# AP_AT42QT2120.net
KiCad netlist of a schematic drawn in EAGLE
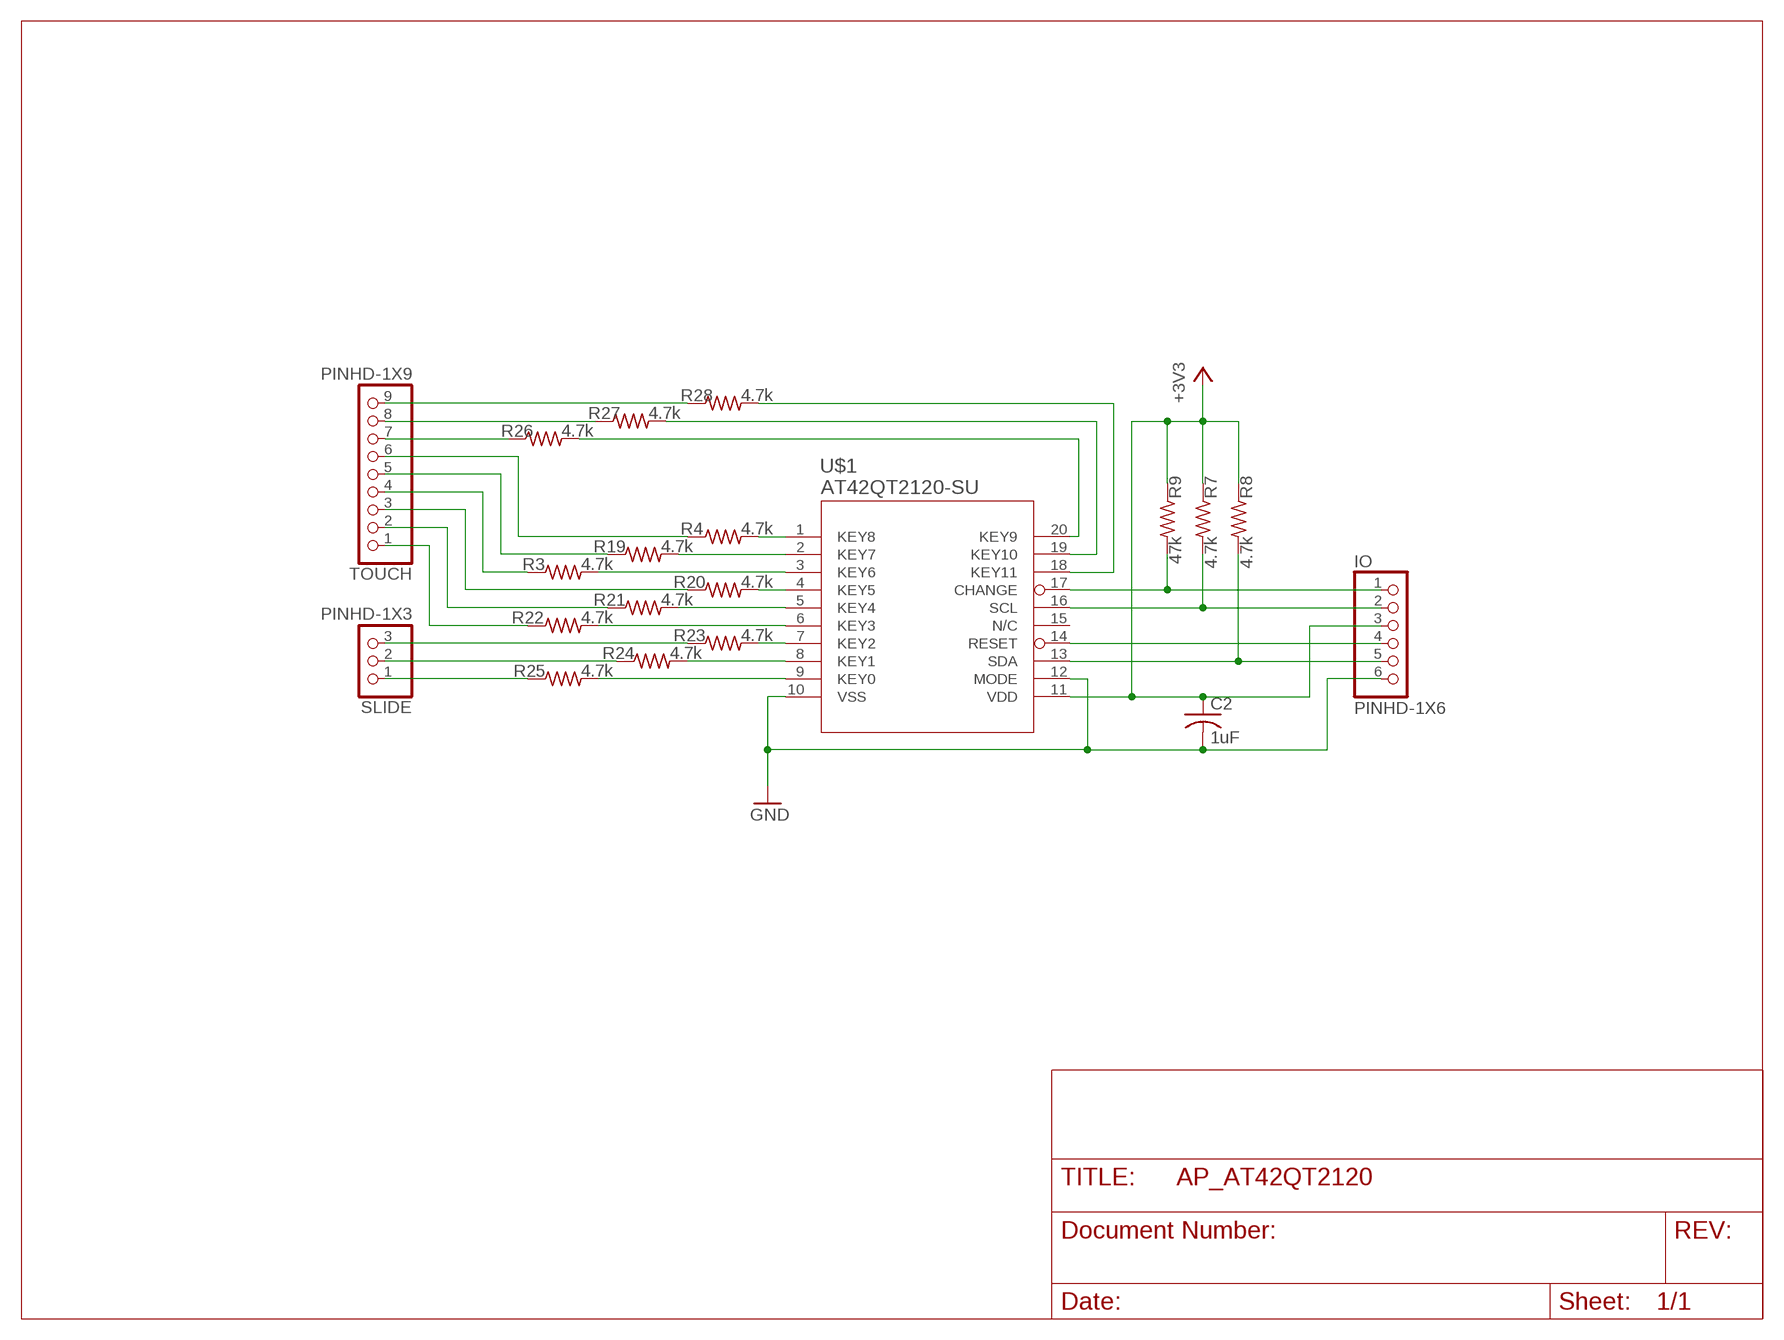
[diagram p0: schematic, sheet 1]

(export (version "E")
  (design (tool "Eeschema 10.0.6"))
  (components
    (comp (ref "C2")
      (value "1uF")
      (footprint "eagle-import:C1206")
      (libsource (lib "eagle-import") (part "C-USC1206"))
    )
    (comp (ref "IO")
      (value "PINHD-1X6")
      (footprint "eagle-import:1X06")
      (libsource (lib "eagle-import") (part "PINHD-1X6"))
    )
    (comp (ref "R3")
      (value "4.7k")
      (footprint "eagle-import:R1206")
      (libsource (lib "eagle-import") (part "R-US_R1206"))
    )
    (comp (ref "R4")
      (value "4.7k")
      (footprint "eagle-import:R1206")
      (libsource (lib "eagle-import") (part "R-US_R1206"))
    )
    (comp (ref "R7")
      (value "4.7k")
      (footprint "eagle-import:R1206")
      (libsource (lib "eagle-import") (part "R-US_R1206"))
    )
    (comp (ref "R8")
      (value "4.7k")
      (footprint "eagle-import:R1206")
      (libsource (lib "eagle-import") (part "R-US_R1206"))
    )
    (comp (ref "R9")
      (value "47k")
      (footprint "eagle-import:R1206")
      (libsource (lib "eagle-import") (part "R-US_R1206"))
    )
    (comp (ref "R19")
      (value "4.7k")
      (footprint "eagle-import:R1206")
      (libsource (lib "eagle-import") (part "R-US_R1206"))
    )
    (comp (ref "R20")
      (value "4.7k")
      (footprint "eagle-import:R1206")
      (libsource (lib "eagle-import") (part "R-US_R1206"))
    )
    (comp (ref "R21")
      (value "4.7k")
      (footprint "eagle-import:R1206")
      (libsource (lib "eagle-import") (part "R-US_R1206"))
    )
    (comp (ref "R22")
      (value "4.7k")
      (footprint "eagle-import:R1206")
      (libsource (lib "eagle-import") (part "R-US_R1206"))
    )
    (comp (ref "R23")
      (value "4.7k")
      (footprint "eagle-import:R1206")
      (libsource (lib "eagle-import") (part "R-US_R1206"))
    )
    (comp (ref "R24")
      (value "4.7k")
      (footprint "eagle-import:R1206")
      (libsource (lib "eagle-import") (part "R-US_R1206"))
    )
    (comp (ref "R25")
      (value "4.7k")
      (footprint "eagle-import:R1206")
      (libsource (lib "eagle-import") (part "R-US_R1206"))
    )
    (comp (ref "R26")
      (value "4.7k")
      (footprint "eagle-import:R1206")
      (libsource (lib "eagle-import") (part "R-US_R1206"))
    )
    (comp (ref "R27")
      (value "4.7k")
      (footprint "eagle-import:R1206")
      (libsource (lib "eagle-import") (part "R-US_R1206"))
    )
    (comp (ref "R28")
      (value "4.7k")
      (footprint "eagle-import:R1206")
      (libsource (lib "eagle-import") (part "R-US_R1206"))
    )
    (comp (ref "SLIDE")
      (value "PINHD-1X3")
      (footprint "eagle-import:1X03")
      (libsource (lib "eagle-import") (part "PINHD-1X3"))
    )
    (comp (ref "TOUCH")
      (value "PINHD-1X9")
      (footprint "eagle-import:1X09")
      (libsource (lib "eagle-import") (part "PINHD-1X9"))
    )
    (comp (ref "U$1")
      (value "AT42QT2120-SU")
      (footprint "eagle-import:SOIC20")
      (libsource (lib "eagle-import") (part "AT42QT2120-SU"))
    )
  )
  (nets
    (net (code "1") (name "+3V3") (class "Default")
      (node (ref "C2") (pin "1") (pinfunction "1_1") (pintype "passive"))
      (node (ref "IO") (pin "3") (pinfunction "3_3") (pintype "passive"))
      (node (ref "R7") (pin "1") (pinfunction "1_1") (pintype "passive"))
      (node (ref "R8") (pin "1") (pinfunction "1_1") (pintype "passive"))
      (node (ref "R9") (pin "1") (pinfunction "1_1") (pintype "passive"))
      (node (ref "U$1") (pin "11") (pinfunction "VDD_11") (pintype "power_in"))
    )
    (net (code "2") (name "GND") (class "Default")
      (node (ref "C2") (pin "2") (pinfunction "2_2") (pintype "passive"))
      (node (ref "IO") (pin "6") (pinfunction "6_6") (pintype "passive"))
      (node (ref "U$1") (pin "10") (pinfunction "VSS_10") (pintype "passive"))
      (node (ref "U$1") (pin "12") (pinfunction "MODE_12") (pintype "passive"))
    )
    (net (code "3") (name "Net-(R3-Pad1)") (class "Default")
      (node (ref "R3") (pin "1") (pinfunction "1_1") (pintype "passive"))
      (node (ref "TOUCH") (pin "4") (pinfunction "4_4") (pintype "passive"))
    )
    (net (code "4") (name "Net-(R4-Pad1)") (class "Default")
      (node (ref "R4") (pin "1") (pinfunction "1_1") (pintype "passive"))
      (node (ref "TOUCH") (pin "6") (pinfunction "6_6") (pintype "passive"))
    )
    (net (code "5") (name "Net-(R19-Pad1)") (class "Default")
      (node (ref "R19") (pin "1") (pinfunction "1_1") (pintype "passive"))
      (node (ref "TOUCH") (pin "5") (pinfunction "5_5") (pintype "passive"))
    )
    (net (code "6") (name "Net-(R20-Pad1)") (class "Default")
      (node (ref "R20") (pin "1") (pinfunction "1_1") (pintype "passive"))
      (node (ref "TOUCH") (pin "3") (pinfunction "3_3") (pintype "passive"))
    )
    (net (code "7") (name "Net-(R21-Pad1)") (class "Default")
      (node (ref "R21") (pin "1") (pinfunction "1_1") (pintype "passive"))
      (node (ref "TOUCH") (pin "2") (pinfunction "2_2") (pintype "passive"))
    )
    (net (code "8") (name "Net-(R22-Pad1)") (class "Default")
      (node (ref "R22") (pin "1") (pinfunction "1_1") (pintype "passive"))
      (node (ref "TOUCH") (pin "1") (pinfunction "1_1") (pintype "passive"))
    )
    (net (code "9") (name "Net-(R23-Pad1)") (class "Default")
      (node (ref "R23") (pin "1") (pinfunction "1_1") (pintype "passive"))
      (node (ref "SLIDE") (pin "3") (pinfunction "3_3") (pintype "passive"))
    )
    (net (code "10") (name "Net-(R24-Pad1)") (class "Default")
      (node (ref "R24") (pin "1") (pinfunction "1_1") (pintype "passive"))
      (node (ref "SLIDE") (pin "2") (pinfunction "2_2") (pintype "passive"))
    )
    (net (code "11") (name "Net-(R25-Pad1)") (class "Default")
      (node (ref "R25") (pin "1") (pinfunction "1_1") (pintype "passive"))
      (node (ref "SLIDE") (pin "1") (pinfunction "1_1") (pintype "passive"))
    )
    (net (code "12") (name "Net-(R26-Pad1)") (class "Default")
      (node (ref "R26") (pin "1") (pinfunction "1_1") (pintype "passive"))
      (node (ref "TOUCH") (pin "7") (pinfunction "7_7") (pintype "passive"))
    )
    (net (code "13") (name "Net-(R27-Pad1)") (class "Default")
      (node (ref "R27") (pin "1") (pinfunction "1_1") (pintype "passive"))
      (node (ref "TOUCH") (pin "8") (pinfunction "8_8") (pintype "passive"))
    )
    (net (code "14") (name "Net-(R28-Pad1)") (class "Default")
      (node (ref "R28") (pin "1") (pinfunction "1_1") (pintype "passive"))
      (node (ref "TOUCH") (pin "9") (pinfunction "9_9") (pintype "passive"))
    )
    (net (code "15") (name "Net-(U$1-CHANGE)") (class "Default")
      (node (ref "IO") (pin "1") (pinfunction "1_1") (pintype "passive"))
      (node (ref "R9") (pin "2") (pinfunction "2_2") (pintype "passive"))
      (node (ref "U$1") (pin "17") (pinfunction "CHANGE_17") (pintype "input"))
    )
    (net (code "16") (name "Net-(U$1-KEY0)") (class "Default")
      (node (ref "R25") (pin "2") (pinfunction "2_2") (pintype "passive"))
      (node (ref "U$1") (pin "9") (pinfunction "KEY0_9") (pintype "bidirectional"))
    )
    (net (code "17") (name "Net-(U$1-KEY1)") (class "Default")
      (node (ref "R24") (pin "2") (pinfunction "2_2") (pintype "passive"))
      (node (ref "U$1") (pin "8") (pinfunction "KEY1_8") (pintype "bidirectional"))
    )
    (net (code "18") (name "Net-(U$1-KEY2)") (class "Default")
      (node (ref "R23") (pin "2") (pinfunction "2_2") (pintype "passive"))
      (node (ref "U$1") (pin "7") (pinfunction "KEY2_7") (pintype "bidirectional"))
    )
    (net (code "19") (name "Net-(U$1-KEY3)") (class "Default")
      (node (ref "R22") (pin "2") (pinfunction "2_2") (pintype "passive"))
      (node (ref "U$1") (pin "6") (pinfunction "KEY3_6") (pintype "bidirectional"))
    )
    (net (code "20") (name "Net-(U$1-KEY4)") (class "Default")
      (node (ref "R21") (pin "2") (pinfunction "2_2") (pintype "passive"))
      (node (ref "U$1") (pin "5") (pinfunction "KEY4_5") (pintype "bidirectional"))
    )
    (net (code "21") (name "Net-(U$1-KEY5)") (class "Default")
      (node (ref "R20") (pin "2") (pinfunction "2_2") (pintype "passive"))
      (node (ref "U$1") (pin "4") (pinfunction "KEY5_4") (pintype "bidirectional"))
    )
    (net (code "22") (name "Net-(U$1-KEY6)") (class "Default")
      (node (ref "R3") (pin "2") (pinfunction "2_2") (pintype "passive"))
      (node (ref "U$1") (pin "3") (pinfunction "KEY6_3") (pintype "bidirectional"))
    )
    (net (code "23") (name "Net-(U$1-KEY7)") (class "Default")
      (node (ref "R19") (pin "2") (pinfunction "2_2") (pintype "passive"))
      (node (ref "U$1") (pin "2") (pinfunction "KEY7_2") (pintype "bidirectional"))
    )
    (net (code "24") (name "Net-(U$1-KEY8)") (class "Default")
      (node (ref "R4") (pin "2") (pinfunction "2_2") (pintype "passive"))
      (node (ref "U$1") (pin "1") (pinfunction "KEY8_1") (pintype "bidirectional"))
    )
    (net (code "25") (name "Net-(U$1-KEY9)") (class "Default")
      (node (ref "R26") (pin "2") (pinfunction "2_2") (pintype "passive"))
      (node (ref "U$1") (pin "20") (pinfunction "KEY9_20") (pintype "bidirectional"))
    )
    (net (code "26") (name "Net-(U$1-KEY10)") (class "Default")
      (node (ref "R27") (pin "2") (pinfunction "2_2") (pintype "passive"))
      (node (ref "U$1") (pin "19") (pinfunction "KEY10_19") (pintype "bidirectional"))
    )
    (net (code "27") (name "Net-(U$1-KEY11)") (class "Default")
      (node (ref "R28") (pin "2") (pinfunction "2_2") (pintype "passive"))
      (node (ref "U$1") (pin "18") (pinfunction "KEY11_18") (pintype "bidirectional"))
    )
    (net (code "28") (name "Net-(U$1-RESET)") (class "Default")
      (node (ref "IO") (pin "4") (pinfunction "4_4") (pintype "passive"))
      (node (ref "U$1") (pin "14") (pinfunction "RESET_14") (pintype "passive"))
    )
    (net (code "29") (name "Net-(U$1-SCL)") (class "Default")
      (node (ref "IO") (pin "2") (pinfunction "2_2") (pintype "passive"))
      (node (ref "R7") (pin "2") (pinfunction "2_2") (pintype "passive"))
      (node (ref "U$1") (pin "16") (pinfunction "SCL_16") (pintype "bidirectional"))
    )
    (net (code "30") (name "Net-(U$1-SDA)") (class "Default")
      (node (ref "IO") (pin "5") (pinfunction "5_5") (pintype "passive"))
      (node (ref "R8") (pin "2") (pinfunction "2_2") (pintype "passive"))
      (node (ref "U$1") (pin "13") (pinfunction "SDA_13") (pintype "bidirectional"))
    )
    (net (code "31") (name "unconnected-(U$1-N{slash}C-Pad15)") (class "Default")
      (node (ref "U$1") (pin "15") (pinfunction "N/C_15") (pintype "no_connect"))
    )
  )
)
